# Regulador_5v_FF21.net
KiCad netlist of a schematic drawn in Altium Designer
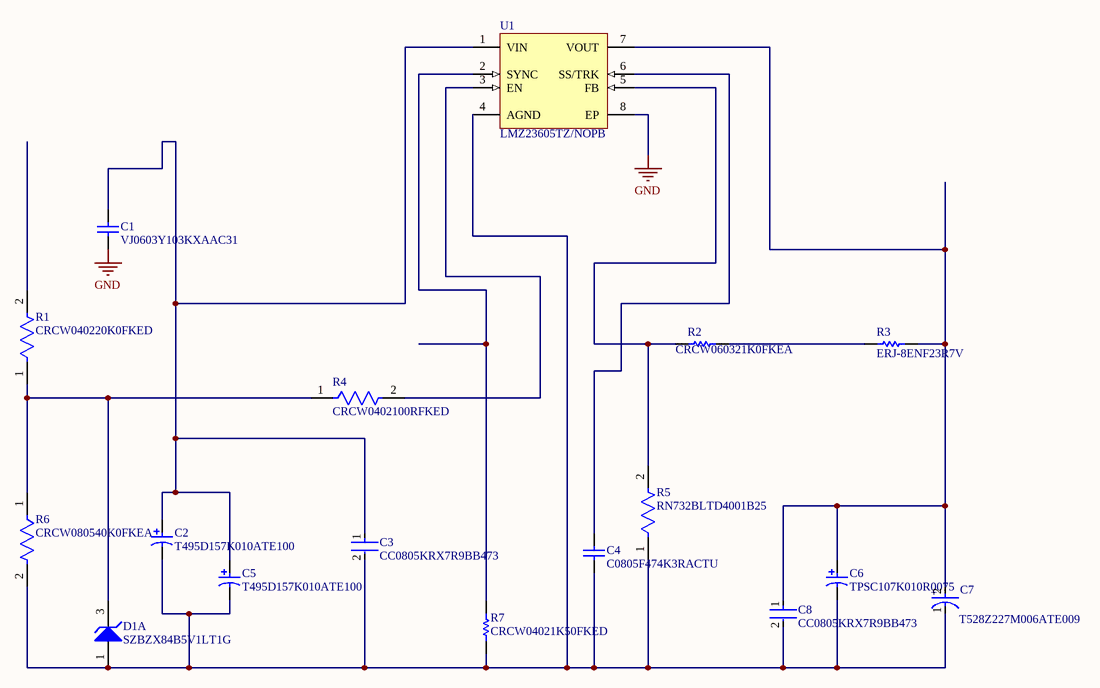
[diagram p0: Regulador_5v_FF21.SchDoc]

(export (version "E")
  (design (tool "Eeschema 10.0.6"))
  (components
    (comp (ref "C1")
      (value "VJ0603Y103KXAAC31")
      (footprint "CAPC1608X97X38LL15T08")
      (fields (field (name "MANUFACTURER") "Vitramon"))
      (libsource (lib "Altium Content Vault") (part "CAP"))
    )
    (comp (ref "C2")
      (value "T495D157K010ATE100")
      (footprint "KEMT-T495-D_L")
      (description "Capacitor, Tantalum, 150 uF, +/- 10%, 10 V, -55 to 125 degC, 2-Pin SMD, RoHS, Tape and Reel")
      (fields (field (name "MANUFACTURER") "Kemet"))
      (libsource (lib "Altium Content Vault") (part "CAP-P-2"))
    )
    (comp (ref "C3")
      (value "CC0805KRX7R9BB473")
      (footprint "FP-CC0805-0_85-MFG")
      (description "CAP CER 0.047UF 50V X7R 0805")
      (fields
        (field (name "OCTOPART") "https://octopart.com/cc0805krx7r9bb473-yageo-42181304")
        (field (name "TOLERANCE") "0.1")
      )
      (libsource (lib "Altium Content Vault") (part "11868f565c42a9108669ba33697ecf6"))
    )
    (comp (ref "C4")
      (value "C0805F474K3RACTU")
      (footprint "CAPC2013X140X50ML20T25")
      (fields (field (name "MANUFACTURER") "Kemet"))
      (libsource (lib "Altium Content Vault") (part "CAP"))
    )
    (comp (ref "C5")
      (value "T495D157K010ATE100")
      (footprint "KEMT-T495-D_L")
      (description "Capacitor, Tantalum, 150 uF, +/- 10%, 10 V, -55 to 125 degC, 2-Pin SMD, RoHS, Tape and Reel")
      (fields (field (name "MANUFACTURER") "Kemet"))
      (libsource (lib "Altium Content Vault") (part "CAP-P-2"))
    )
    (comp (ref "C6")
      (value "TPSC107K010R0075")
      (footprint "AVX-C2312_L")
      (description "TPS Series, Low ESR, 100 uF, +/- 10%, 10 V, -55 to 125 degC, 2-Pin SMD (2312), RoHS, Tape and Reel")
      (fields (field (name "VOLTAGE") "10VDC") (field (name "MANUFACTURER") "AVX"))
      (libsource (lib "Altium Content Vault") (part "CAP-P-2"))
    )
    (comp (ref "C7")
      (value "T528Z227M006ATE009")
      (footprint "FP-T528Z227M006ATE009-MFG")
      (description "CAP TANT POLY 220UF 6.3V 2917")
      (fields (field (name "TOLERANCE") "20%"))
      (libsource (lib "Altium Content Vault") (part "203bc49f2ac43e59fd269a8c329ed05"))
    )
    (comp (ref "C8")
      (value "CC0805KRX7R9BB473")
      (footprint "FP-CC0805-0_85-MFG")
      (description "CAP CER 0.047UF 50V X7R 0805")
      (fields
        (field (name "OCTOPART") "https://octopart.com/cc0805krx7r9bb473-yageo-42181304")
        (field (name "TOLERANCE") "0.1")
      )
      (libsource (lib "Altium Content Vault") (part "11868f565c42a9108669ba33697ecf6"))
    )
    (comp (ref "D1")
      (value "SZBZX84B5V1LT1G")
      (footprint "ONSC-SOT-23-3-318-08_V")
      (description "Zener Voltage Regulator, 225 mW, 3-Pin SOT-23, Pb-Free, Tape and Reel")
      (fields (field (name "MANUFACTURER") "On Semiconductor"))
      (libsource (lib "Altium Content Vault") (part "ONSC-A1K3-3"))
    )
    (comp (ref "R1")
      (value "CRCW040220K0FKED")
      (footprint "FP-CRCW0402-e3-IPC_B")
      (description "RES Thick Film, 20kΩ, 1%, 0.063W, 100ppm/°C, 0402")
      (fields (field (name "TOLERANCE") "1%"))
      (libsource (lib "Altium Content Vault") (part "1029c3af85768c4190bb7ad29bc67b5"))
    )
    (comp (ref "R2")
      (value "CRCW060321K0FKEA")
      (footprint "RESC1609X50X30LL10T20")
      (fields (field (name "MANUFACTURER") "Vishay Dale"))
      (libsource (lib "Altium Content Vault") (part "RES"))
    )
    (comp (ref "R3")
      (value "ERJ-8ENF23R7V")
      (footprint "RESC3216X70X50NL05T20")
      (fields (field (name "MANUFACTURER") "Panasonic"))
      (libsource (lib "Altium Content Vault") (part "RES"))
    )
    (comp (ref "R4")
      (value "CRCW0402100RFKED")
      (footprint "FP-CRCW0402-e3-IPC_C")
      (description "RES Thick Film, 100Ω, 1%, 0.063W, 100ppm/°C, 0402")
      (fields (field (name "TOLERANCE") "1%"))
      (libsource (lib "Altium Content Vault") (part "1029c3af85768c4190bb7ad29bc67b5"))
    )
    (comp (ref "R5")
      (value "RN732BLTD4001B25")
      (footprint "FP-RN732B-MFG")
      (description "4kΩ ±0.1% 0.125W, 1/8W Chip Resistor 1206 (3216 Metric) Moisture Resistant Thin Film")
      (fields (field (name "TOLERANCE") "0.1%"))
      (libsource (lib "Altium Content Vault") (part "1029c3af85768c4190bb7ad29bc67b5"))
    )
    (comp (ref "R6")
      (value "CRCW080540K0FKEA")
      (footprint "FP-CRCW0805-e3-MFG")
      (description "RES Thick Film, 40kΩ, 1%, 0.125W, 100ppm/°C, 0805")
      (fields (field (name "TOLERANCE") "1%"))
      (libsource (lib "Altium Content Vault") (part "1029c3af85768c4190bb7ad29bc67b5"))
    )
    (comp (ref "R7")
      (value "CRCW04021K50FKED")
      (footprint "RESC1005X40X25NL05T05")
      (fields (field (name "MANUFACTURER") "Vishay Dale"))
      (libsource (lib "Altium Content Vault") (part "RES"))
    )
    (comp (ref "U1")
      (value "LMZ23605TZ/NOPB")
      (footprint "NDW0007A_V")
      (description "5A SIMPLE SWITCHER® Power Module with 36V Maximum Input Voltage, 7 pin TO-PMOD, 45 Rail")
      (fields (field (name "MANUFACTURER") "Texas Instruments"))
      (libsource (lib "Altium Content Vault") (part "PM-REG-LMZ23605-8"))
    )
  )
  (nets
    (net (code "1") (name "GND") (class "Default")
      (node (ref "C1") (pin "1") (pinfunction "1_1") (pintype "passive"))
      (node (ref "U1") (pin "8") (pinfunction "EP_8") (pintype "power_in"))
    )
    (net (code "2") (name "Net-(C7-A)") (class "Default")
      (node (ref "C6") (pin "1") (pinfunction "1_1") (pintype "passive"))
      (node (ref "C7") (pin "2") (pinfunction "A_2") (pintype "passive"))
      (node (ref "C8") (pin "1") (pinfunction "1_1") (pintype "passive"))
      (node (ref "R3") (pin "2") (pinfunction "2_2") (pintype "passive"))
      (node (ref "U1") (pin "7") (pinfunction "VOUT_7") (pintype "power_in"))
    )
    (net (code "3") (name "Net-(C7-C)") (class "Default")
      (node (ref "C2") (pin "2") (pinfunction "2_2") (pintype "passive"))
      (node (ref "C3") (pin "2") (pinfunction "2_2") (pintype "passive"))
      (node (ref "C4") (pin "1") (pinfunction "1_1") (pintype "passive"))
      (node (ref "C5") (pin "2") (pinfunction "2_2") (pintype "passive"))
      (node (ref "C6") (pin "2") (pinfunction "2_2") (pintype "passive"))
      (node (ref "C7") (pin "1") (pinfunction "C_1") (pintype "passive"))
      (node (ref "C8") (pin "2") (pinfunction "2_2") (pintype "passive"))
      (node (ref "D1") (pin "1") (pinfunction "A_1") (pintype "passive"))
      (node (ref "R5") (pin "1") (pinfunction "1_1") (pintype "passive"))
      (node (ref "R6") (pin "2") (pinfunction "2_2") (pintype "passive"))
      (node (ref "R7") (pin "1") (pinfunction "1_1") (pintype "passive"))
      (node (ref "U1") (pin "4") (pinfunction "AGND_4") (pintype "power_in"))
    )
    (net (code "4") (name "Net-(D1A-K)") (class "Default")
      (node (ref "D1") (pin "3") (pinfunction "K_3") (pintype "passive"))
      (node (ref "R1") (pin "1") (pinfunction "1_1") (pintype "passive"))
      (node (ref "R4") (pin "1") (pinfunction "1_1") (pintype "passive"))
      (node (ref "R6") (pin "1") (pinfunction "1_1") (pintype "passive"))
    )
    (net (code "5") (name "Net-(R2-Pad2)") (class "Default")
      (node (ref "R2") (pin "2") (pinfunction "2_2") (pintype "passive"))
      (node (ref "R3") (pin "1") (pinfunction "1_1") (pintype "passive"))
    )
    (net (code "6") (name "Net-(U1-EN)") (class "Default")
      (node (ref "R4") (pin "2") (pinfunction "2_2") (pintype "passive"))
      (node (ref "U1") (pin "3") (pinfunction "EN_3") (pintype "input"))
    )
    (net (code "7") (name "Net-(U1-FB)") (class "Default")
      (node (ref "R2") (pin "1") (pinfunction "1_1") (pintype "passive"))
      (node (ref "R5") (pin "2") (pinfunction "2_2") (pintype "passive"))
      (node (ref "U1") (pin "5") (pinfunction "FB_5") (pintype "input"))
    )
    (net (code "8") (name "Net-(U1-SS{slash}TRK)") (class "Default")
      (node (ref "C4") (pin "2") (pinfunction "2_2") (pintype "passive"))
      (node (ref "U1") (pin "6") (pinfunction "SS/TRK_6") (pintype "input"))
    )
    (net (code "9") (name "Net-(U1-SYNC)") (class "Default")
      (node (ref "R7") (pin "2") (pinfunction "2_2") (pintype "passive"))
      (node (ref "U1") (pin "2") (pinfunction "SYNC_2") (pintype "input"))
    )
    (net (code "10") (name "Net-(U1-VIN)") (class "Default")
      (node (ref "C1") (pin "2") (pinfunction "2_2") (pintype "passive"))
      (node (ref "C2") (pin "1") (pinfunction "1_1") (pintype "passive"))
      (node (ref "C3") (pin "1") (pinfunction "1_1") (pintype "passive"))
      (node (ref "C5") (pin "1") (pinfunction "1_1") (pintype "passive"))
      (node (ref "U1") (pin "1") (pinfunction "VIN_1") (pintype "power_in"))
    )
    (net (code "11") (name "unconnected-(R1-Pad2)") (class "Default")
      (node (ref "R1") (pin "2") (pinfunction "2_2") (pintype "passive"))
    )
  )
)
